# SCH_Gantry-Sensor-PCB-SMD-2_0_2025-12-20.net
KiCad netlist of a schematic drawn in EasyEDA
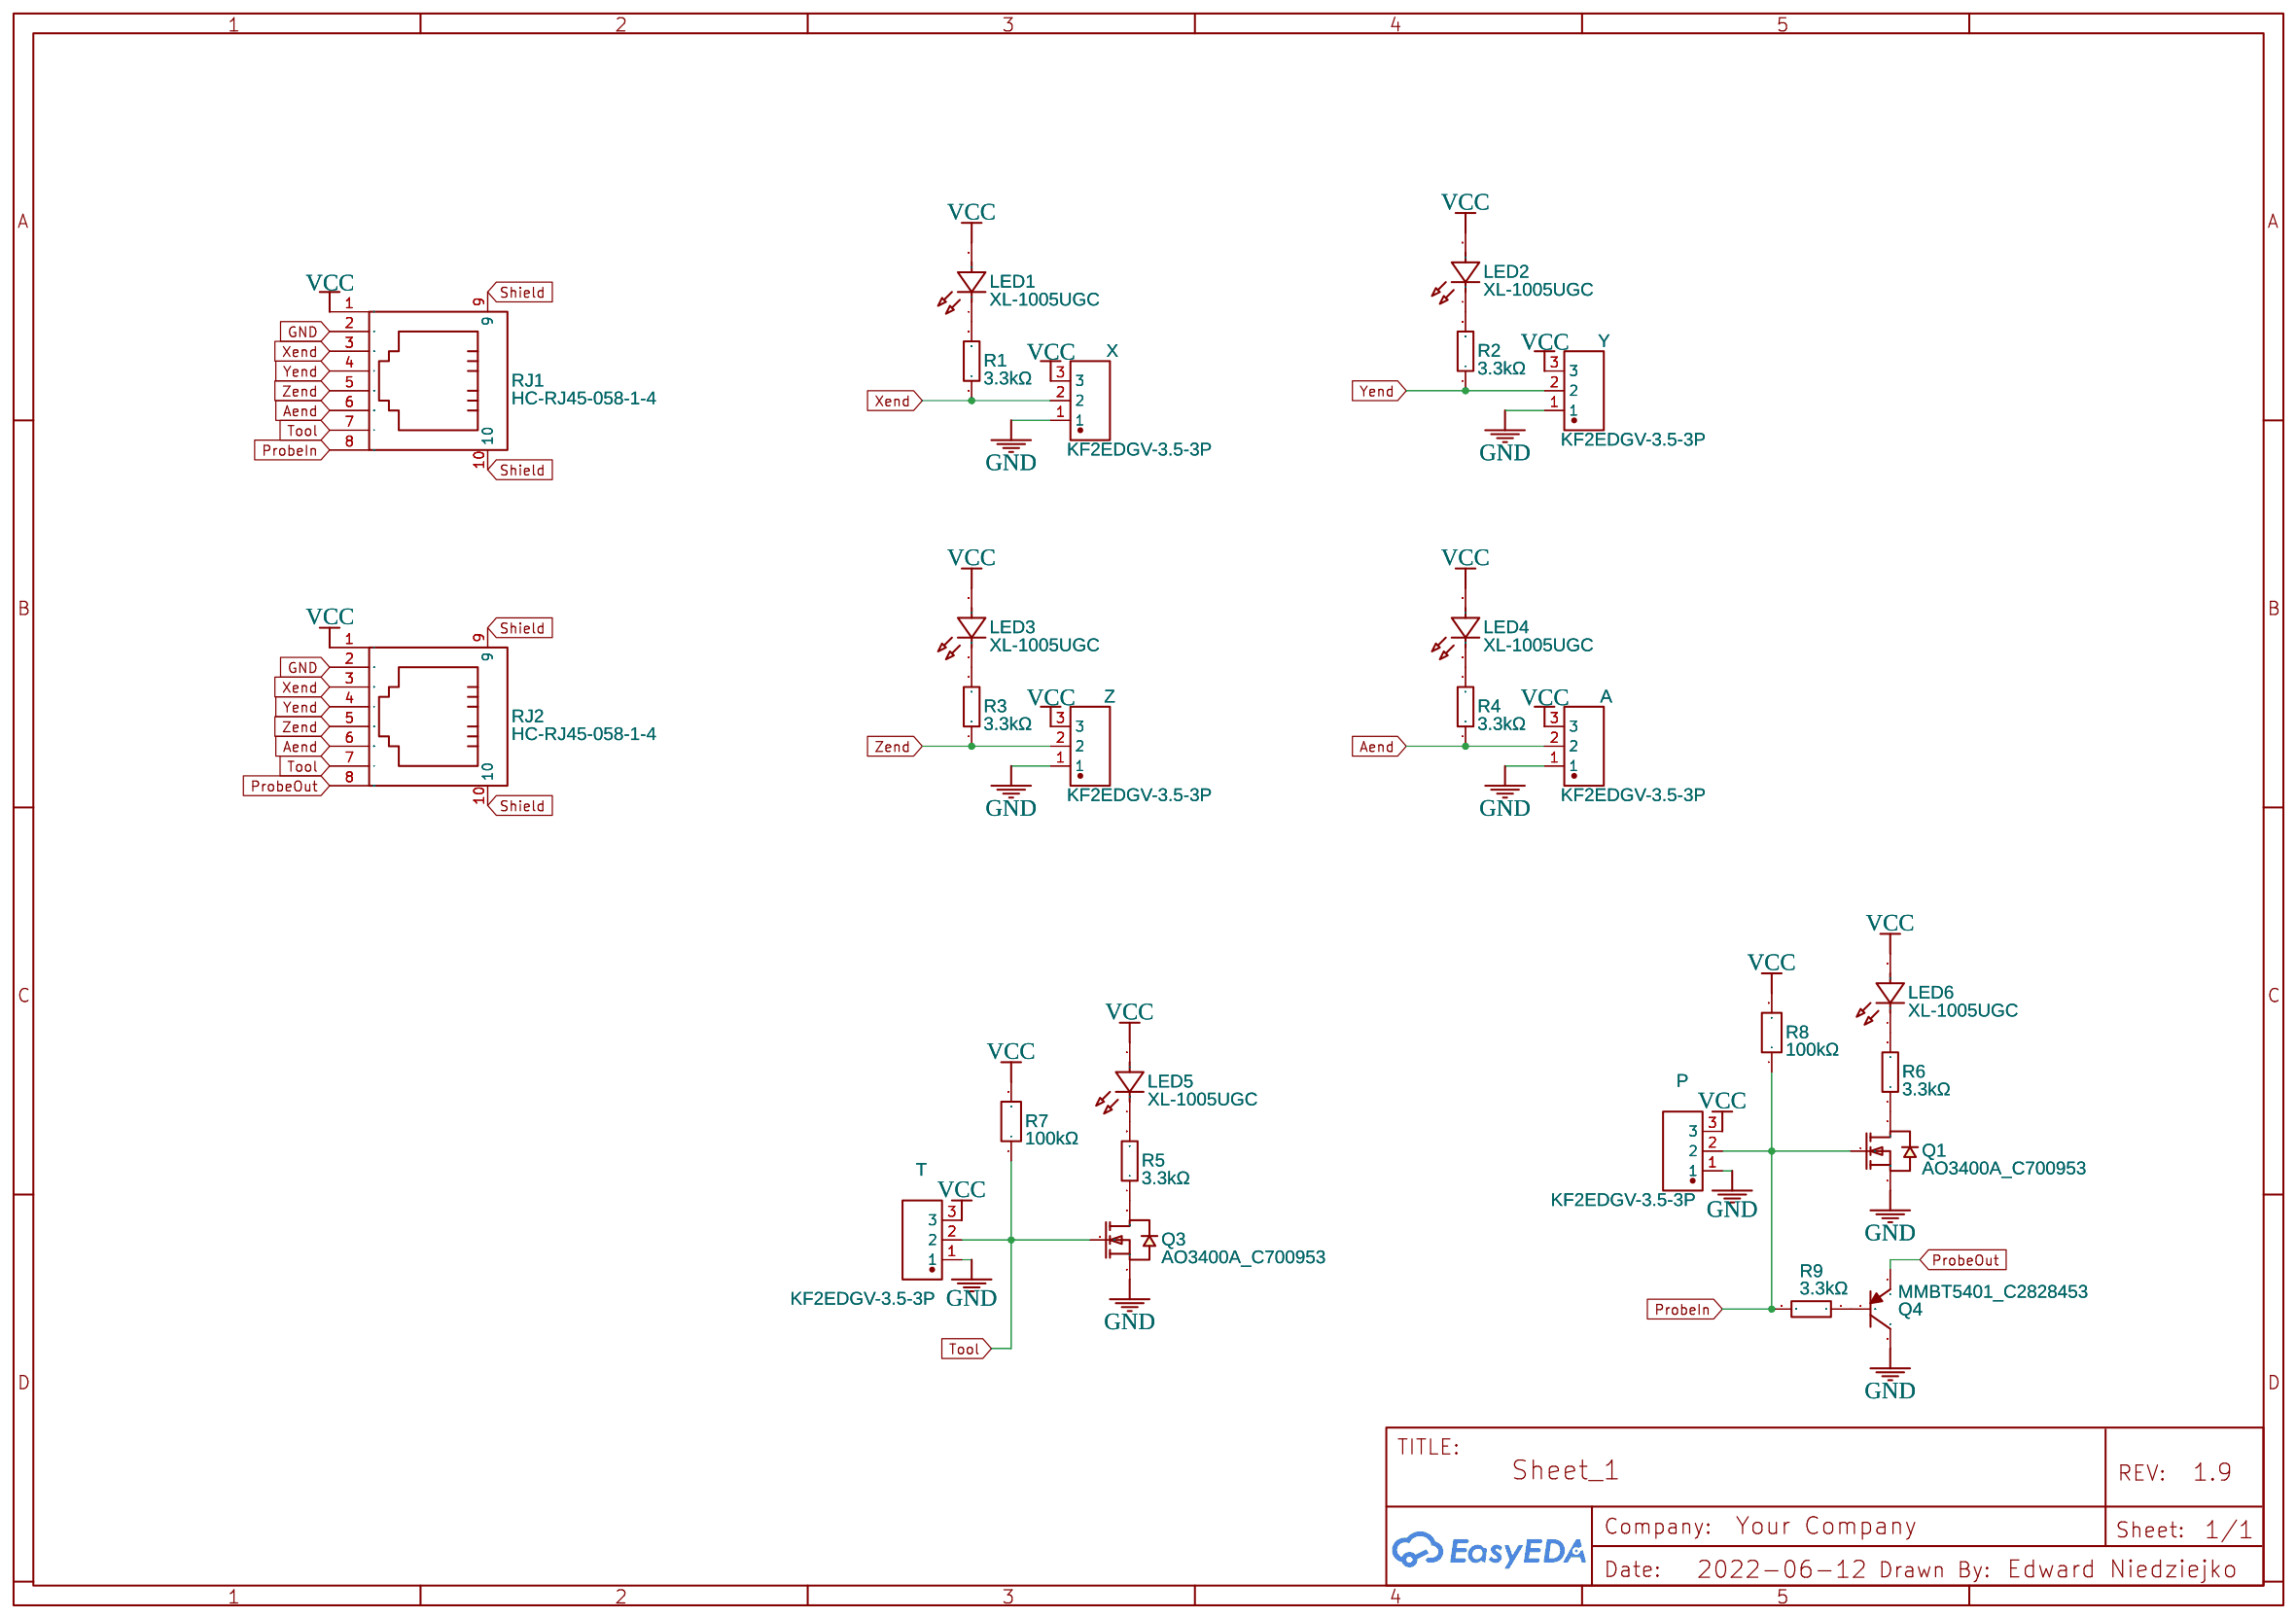
[diagram p0: schematic sheet]

(export (version "E")
  (design (tool "Eeschema 10.0.6"))
  (components
    (comp (ref "A")
      (value "KF2EDGV-3.5-3P")
      (fields (field (name "Manufacturer") "KEFA(科发)"))
      (libsource (lib "") (part "KF2EDGV-3.5-3P"))
    )
    (comp (ref "LED1")
      (value "XL-1005UGC")
      (fields (field (name "Manufacturer") "XINGLIGHT(成兴光)"))
      (libsource (lib "") (part "XL-1005UGC"))
    )
    (comp (ref "LED2")
      (value "XL-1005UGC")
      (fields (field (name "Manufacturer") "XINGLIGHT(成兴光)"))
      (libsource (lib "") (part "XL-1005UGC"))
    )
    (comp (ref "LED3")
      (value "XL-1005UGC")
      (fields (field (name "Manufacturer") "XINGLIGHT(成兴光)"))
      (libsource (lib "") (part "XL-1005UGC"))
    )
    (comp (ref "LED4")
      (value "XL-1005UGC")
      (fields (field (name "Manufacturer") "XINGLIGHT(成兴光)"))
      (libsource (lib "") (part "XL-1005UGC"))
    )
    (comp (ref "LED5")
      (value "XL-1005UGC")
      (fields (field (name "Manufacturer") "XINGLIGHT(成兴光)"))
      (libsource (lib "") (part "XL-1005UGC"))
    )
    (comp (ref "LED6")
      (value "XL-1005UGC")
      (fields (field (name "Manufacturer") "XINGLIGHT(成兴光)"))
      (libsource (lib "") (part "XL-1005UGC"))
    )
    (comp (ref "P")
      (value "KF2EDGV-3.5-3P")
      (fields (field (name "Manufacturer") "KEFA(科发)"))
      (libsource (lib "") (part "KF2EDGV-3.5-3P_3"))
    )
    (comp (ref "Q1")
      (value "AO3400A_C700953")
      (fields (field (name "Manufacturer Part") "AO3400A") (field (name "Manufacturer") "HUASHUO(华朔)"))
      (libsource (lib "") (part "AO3400A_C700953"))
    )
    (comp (ref "Q3")
      (value "AO3400A_C700953")
      (fields (field (name "Manufacturer Part") "AO3400A") (field (name "Manufacturer") "HUASHUO(华朔)"))
      (libsource (lib "") (part "AO3400A_C700953"))
    )
    (comp (ref "Q4")
      (value "MMBT5401_C2828453")
      (fields (field (name "Manufacturer Part") "MMBT5401 2L") (field (name "Manufacturer") "CBI(创基)"))
      (libsource (lib "") (part "MMBT5401_C2828453"))
    )
    (comp (ref "R1")
      (value "3.3kΩ")
      (fields (field (name "Manufacturer Part") "CR0402FF3301G") (field (name "Manufacturer") "LIZ(丽智电子)"))
      (libsource (lib "") (part "CR0402FF3301G_1"))
    )
    (comp (ref "R2")
      (value "3.3kΩ")
      (fields (field (name "Manufacturer Part") "CR0402FF3301G") (field (name "Manufacturer") "LIZ(丽智电子)"))
      (libsource (lib "") (part "CR0402FF3301G_1"))
    )
    (comp (ref "R3")
      (value "3.3kΩ")
      (fields (field (name "Manufacturer Part") "CR0402FF3301G") (field (name "Manufacturer") "LIZ(丽智电子)"))
      (libsource (lib "") (part "CR0402FF3301G_1"))
    )
    (comp (ref "R4")
      (value "3.3kΩ")
      (fields (field (name "Manufacturer Part") "CR0402FF3301G") (field (name "Manufacturer") "LIZ(丽智电子)"))
      (libsource (lib "") (part "CR0402FF3301G_1"))
    )
    (comp (ref "R5")
      (value "3.3kΩ")
      (fields (field (name "Manufacturer Part") "CR0402FF3301G") (field (name "Manufacturer") "LIZ(丽智电子)"))
      (libsource (lib "") (part "CR0402FF3301G_1"))
    )
    (comp (ref "R6")
      (value "3.3kΩ")
      (fields (field (name "Manufacturer Part") "CR0402FF3301G") (field (name "Manufacturer") "LIZ(丽智电子)"))
      (libsource (lib "") (part "CR0402FF3301G_1"))
    )
    (comp (ref "R7")
      (value "100kΩ")
      (fields (field (name "Manufacturer Part") "SCR0402F100K") (field (name "Manufacturer") "VO(翔胜)"))
      (libsource (lib "") (part "SCR0402F100K"))
    )
    (comp (ref "R8")
      (value "100kΩ")
      (fields (field (name "Manufacturer Part") "SCR0402F100K") (field (name "Manufacturer") "VO(翔胜)"))
      (libsource (lib "") (part "SCR0402F100K"))
    )
    (comp (ref "R9")
      (value "3.3kΩ")
      (fields (field (name "Manufacturer Part") "CR0402FF3301G") (field (name "Manufacturer") "LIZ(丽智电子)"))
      (libsource (lib "") (part "CR0402FF3301G"))
    )
    (comp (ref "RJ1")
      (value "HC-RJ45-058-1-4")
      (fields (field (name "Manufacturer") "HCTL(华灿天禄)"))
      (libsource (lib "") (part "HC-RJ45-058-1-4"))
    )
    (comp (ref "RJ2")
      (value "HC-RJ45-058-1-4")
      (fields (field (name "Manufacturer") "HCTL(华灿天禄)"))
      (libsource (lib "") (part "HC-RJ45-058-1-4"))
    )
    (comp (ref "T")
      (value "KF2EDGV-3.5-3P")
      (fields (field (name "Manufacturer") "KEFA(科发)"))
      (libsource (lib "") (part "KF2EDGV-3.5-3P_1"))
    )
    (comp (ref "X")
      (value "KF2EDGV-3.5-3P")
      (fields (field (name "Manufacturer") "KEFA(科发)"))
      (libsource (lib "") (part "KF2EDGV-3.5-3P_2"))
    )
    (comp (ref "Y")
      (value "KF2EDGV-3.5-3P")
      (fields (field (name "Manufacturer") "KEFA(科发)"))
      (libsource (lib "") (part "KF2EDGV-3.5-3P_4"))
    )
    (comp (ref "Z")
      (value "KF2EDGV-3.5-3P")
      (fields (field (name "Manufacturer") "KEFA(科发)"))
      (libsource (lib "") (part "KF2EDGV-3.5-3P_5"))
    )
  )
  (nets
    (net (code "1") (name "Aend") (class "Default")
      (node (ref "A") (pin "2") (pinfunction "2_2") (pintype "unspecified"))
      (node (ref "R4") (pin "1") (pinfunction "1_1") (pintype "input"))
      (node (ref "RJ1") (pin "6") (pinfunction "6_6") (pintype "unspecified"))
      (node (ref "RJ2") (pin "6") (pinfunction "6_6") (pintype "unspecified"))
    )
    (net (code "2") (name "GND") (class "Default")
      (node (ref "A") (pin "1") (pinfunction "1_1") (pintype "unspecified"))
      (node (ref "P") (pin "1") (pinfunction "1_1") (pintype "unspecified"))
      (node (ref "Q1") (pin "2") (pinfunction "S_2") (pintype "unspecified"))
      (node (ref "Q3") (pin "2") (pinfunction "S_2") (pintype "unspecified"))
      (node (ref "Q4") (pin "3") (pinfunction "C_3") (pintype "input"))
      (node (ref "RJ1") (pin "2") (pinfunction "2_2") (pintype "unspecified"))
      (node (ref "RJ2") (pin "2") (pinfunction "2_2") (pintype "unspecified"))
      (node (ref "T") (pin "1") (pinfunction "1_1") (pintype "unspecified"))
      (node (ref "X") (pin "1") (pinfunction "1_1") (pintype "unspecified"))
      (node (ref "Y") (pin "1") (pinfunction "1_1") (pintype "unspecified"))
      (node (ref "Z") (pin "1") (pinfunction "1_1") (pintype "unspecified"))
    )
    (net (code "3") (name "Net-(LED1-K)") (class "Default")
      (node (ref "LED1") (pin "1") (pinfunction "K_1") (pintype "unspecified"))
      (node (ref "R1") (pin "2") (pinfunction "2_2") (pintype "input"))
    )
    (net (code "4") (name "Net-(LED2-K)") (class "Default")
      (node (ref "LED2") (pin "1") (pinfunction "K_1") (pintype "unspecified"))
      (node (ref "R2") (pin "2") (pinfunction "2_2") (pintype "input"))
    )
    (net (code "5") (name "Net-(LED3-K)") (class "Default")
      (node (ref "LED3") (pin "1") (pinfunction "K_1") (pintype "unspecified"))
      (node (ref "R3") (pin "2") (pinfunction "2_2") (pintype "input"))
    )
    (net (code "6") (name "Net-(LED4-K)") (class "Default")
      (node (ref "LED4") (pin "1") (pinfunction "K_1") (pintype "unspecified"))
      (node (ref "R4") (pin "2") (pinfunction "2_2") (pintype "input"))
    )
    (net (code "7") (name "Net-(LED5-K)") (class "Default")
      (node (ref "LED5") (pin "1") (pinfunction "K_1") (pintype "unspecified"))
      (node (ref "R5") (pin "2") (pinfunction "2_2") (pintype "input"))
    )
    (net (code "8") (name "Net-(LED6-K)") (class "Default")
      (node (ref "LED6") (pin "1") (pinfunction "K_1") (pintype "unspecified"))
      (node (ref "R6") (pin "2") (pinfunction "2_2") (pintype "input"))
    )
    (net (code "9") (name "Net-(Q1-D)") (class "Default")
      (node (ref "Q1") (pin "3") (pinfunction "D_3") (pintype "unspecified"))
      (node (ref "R6") (pin "1") (pinfunction "1_1") (pintype "input"))
    )
    (net (code "10") (name "Net-(Q3-D)") (class "Default")
      (node (ref "Q3") (pin "3") (pinfunction "D_3") (pintype "unspecified"))
      (node (ref "R5") (pin "1") (pinfunction "1_1") (pintype "input"))
    )
    (net (code "11") (name "Net-(Q4-B)") (class "Default")
      (node (ref "Q4") (pin "2") (pinfunction "B_2") (pintype "input"))
      (node (ref "R9") (pin "1") (pinfunction "1_1") (pintype "input"))
    )
    (net (code "12") (name "ProbeIn") (class "Default")
      (node (ref "P") (pin "2") (pinfunction "2_2") (pintype "unspecified"))
      (node (ref "Q1") (pin "1") (pinfunction "G_1") (pintype "unspecified"))
      (node (ref "R8") (pin "1") (pinfunction "1_1") (pintype "unspecified"))
      (node (ref "R9") (pin "2") (pinfunction "2_2") (pintype "input"))
      (node (ref "RJ1") (pin "8") (pinfunction "8_8") (pintype "unspecified"))
    )
    (net (code "13") (name "ProbeOut") (class "Default")
      (node (ref "Q4") (pin "1") (pinfunction "E_1") (pintype "input"))
      (node (ref "RJ2") (pin "8") (pinfunction "8_8") (pintype "unspecified"))
    )
    (net (code "14") (name "Shield") (class "Default")
      (node (ref "RJ1") (pin "10") (pinfunction "10_10") (pintype "unspecified"))
      (node (ref "RJ1") (pin "9") (pinfunction "9_9") (pintype "unspecified"))
      (node (ref "RJ2") (pin "10") (pinfunction "10_10") (pintype "unspecified"))
      (node (ref "RJ2") (pin "9") (pinfunction "9_9") (pintype "unspecified"))
    )
    (net (code "15") (name "Tool") (class "Default")
      (node (ref "Q3") (pin "1") (pinfunction "G_1") (pintype "unspecified"))
      (node (ref "R7") (pin "1") (pinfunction "1_1") (pintype "unspecified"))
      (node (ref "RJ1") (pin "7") (pinfunction "7_7") (pintype "unspecified"))
      (node (ref "RJ2") (pin "7") (pinfunction "7_7") (pintype "unspecified"))
      (node (ref "T") (pin "2") (pinfunction "2_2") (pintype "unspecified"))
    )
    (net (code "16") (name "VCC") (class "Default")
      (node (ref "A") (pin "3") (pinfunction "3_3") (pintype "unspecified"))
      (node (ref "LED1") (pin "2") (pinfunction "A_2") (pintype "unspecified"))
      (node (ref "LED2") (pin "2") (pinfunction "A_2") (pintype "unspecified"))
      (node (ref "LED3") (pin "2") (pinfunction "A_2") (pintype "unspecified"))
      (node (ref "LED4") (pin "2") (pinfunction "A_2") (pintype "unspecified"))
      (node (ref "LED5") (pin "2") (pinfunction "A_2") (pintype "unspecified"))
      (node (ref "LED6") (pin "2") (pinfunction "A_2") (pintype "unspecified"))
      (node (ref "P") (pin "3") (pinfunction "3_3") (pintype "unspecified"))
      (node (ref "R7") (pin "2") (pinfunction "2_2") (pintype "unspecified"))
      (node (ref "R8") (pin "2") (pinfunction "2_2") (pintype "unspecified"))
      (node (ref "RJ1") (pin "1") (pinfunction "1_1") (pintype "unspecified"))
      (node (ref "RJ2") (pin "1") (pinfunction "1_1") (pintype "unspecified"))
      (node (ref "T") (pin "3") (pinfunction "3_3") (pintype "unspecified"))
      (node (ref "X") (pin "3") (pinfunction "3_3") (pintype "unspecified"))
      (node (ref "Y") (pin "3") (pinfunction "3_3") (pintype "unspecified"))
      (node (ref "Z") (pin "3") (pinfunction "3_3") (pintype "unspecified"))
    )
    (net (code "17") (name "Xend") (class "Default")
      (node (ref "R1") (pin "1") (pinfunction "1_1") (pintype "input"))
      (node (ref "RJ1") (pin "3") (pinfunction "3_3") (pintype "unspecified"))
      (node (ref "RJ2") (pin "3") (pinfunction "3_3") (pintype "unspecified"))
      (node (ref "X") (pin "2") (pinfunction "2_2") (pintype "unspecified"))
    )
    (net (code "18") (name "Yend") (class "Default")
      (node (ref "R2") (pin "1") (pinfunction "1_1") (pintype "input"))
      (node (ref "RJ1") (pin "4") (pinfunction "4_4") (pintype "unspecified"))
      (node (ref "RJ2") (pin "4") (pinfunction "4_4") (pintype "unspecified"))
      (node (ref "Y") (pin "2") (pinfunction "2_2") (pintype "unspecified"))
    )
    (net (code "19") (name "Zend") (class "Default")
      (node (ref "R3") (pin "1") (pinfunction "1_1") (pintype "input"))
      (node (ref "RJ1") (pin "5") (pinfunction "5_5") (pintype "unspecified"))
      (node (ref "RJ2") (pin "5") (pinfunction "5_5") (pintype "unspecified"))
      (node (ref "Z") (pin "2") (pinfunction "2_2") (pintype "unspecified"))
    )
  )
)
